# Zenith.net
KiCad netlist of a schematic drawn in EAGLE
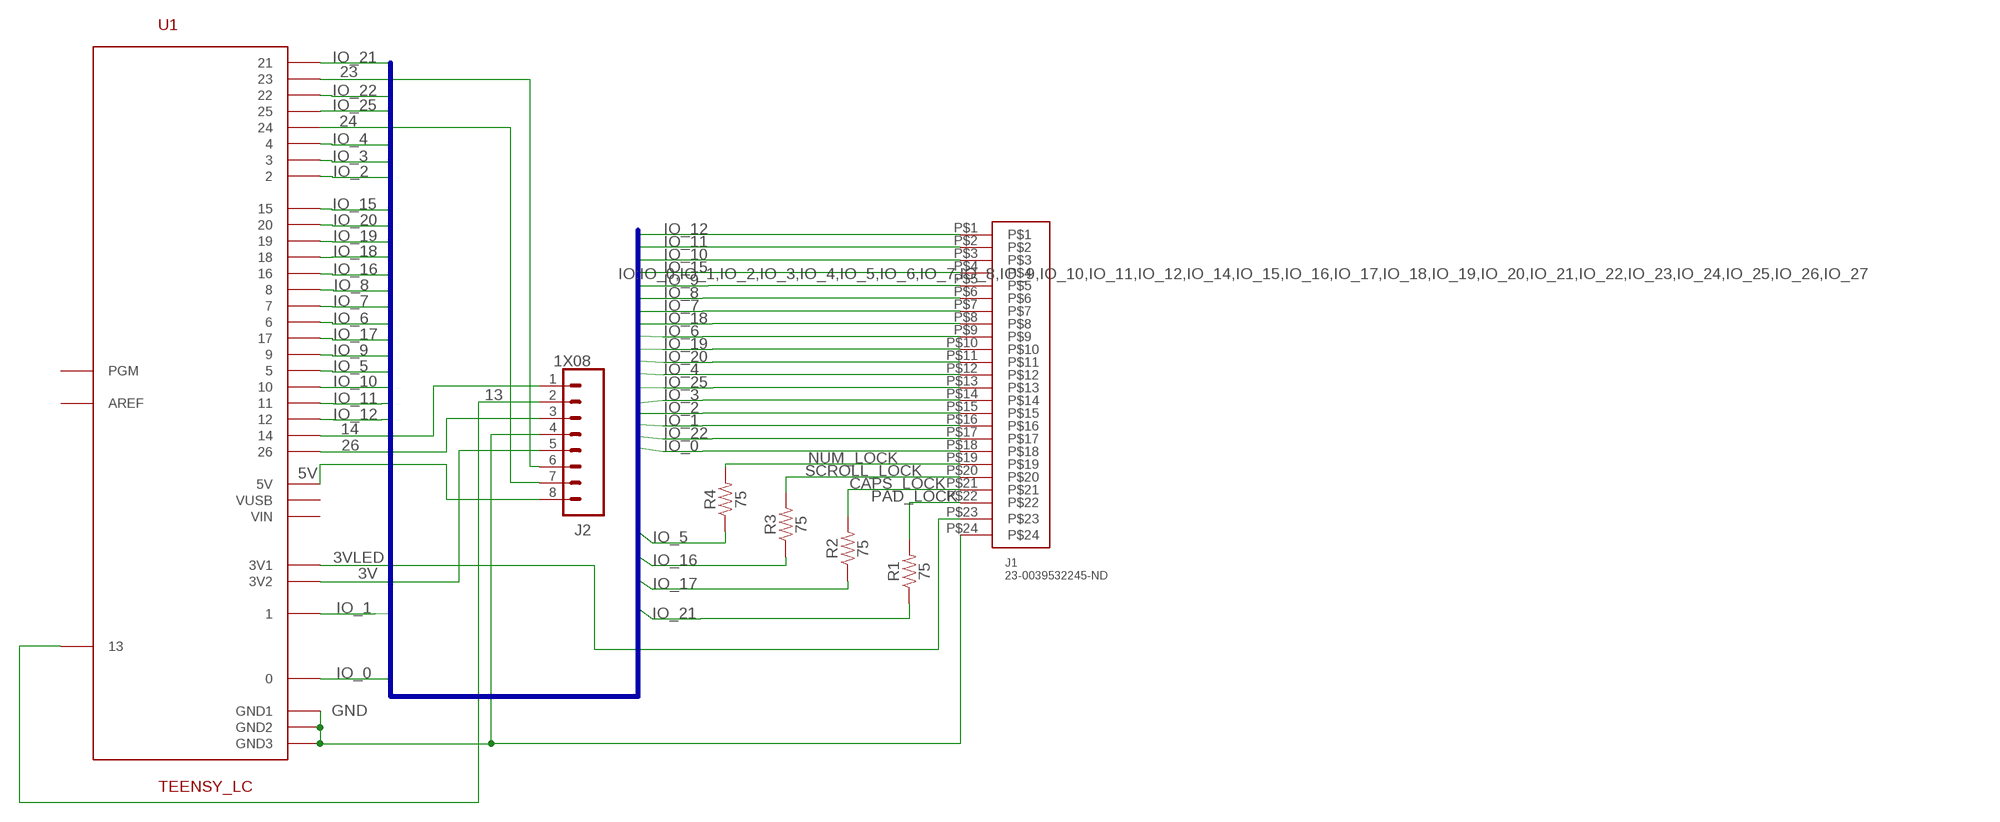
[diagram p0: schematic, sheet 1]

(export (version "E")
  (design (tool "Eeschema 10.0.6"))
  (components
    (comp (ref "J1")
      (value "23-0039532245-ND")
      (footprint "eagle-import:ZENITH_CON")
      (libsource (lib "eagle-import") (part "ZENITH_CON"))
    )
    (comp (ref "J2")
      (value "1X08")
      (footprint "eagle-import:1X08")
      (libsource (lib "eagle-import") (part "CONN_08{dblquote}"))
    )
    (comp (ref "R1")
      (value "75")
      (footprint "eagle-import:AXIAL-0.3")
      (libsource (lib "eagle-import") (part "RESISTOR_AXIAL"))
    )
    (comp (ref "R2")
      (value "75")
      (footprint "eagle-import:AXIAL-0.3")
      (libsource (lib "eagle-import") (part "RESISTOR_AXIAL"))
    )
    (comp (ref "R3")
      (value "75")
      (footprint "eagle-import:AXIAL-0.3")
      (libsource (lib "eagle-import") (part "RESISTOR_AXIAL"))
    )
    (comp (ref "R4")
      (value "75")
      (footprint "eagle-import:AXIAL-0.3")
      (libsource (lib "eagle-import") (part "RESISTOR_AXIAL"))
    )
    (comp (ref "U1")
      (value "TEENSY_LC")
      (footprint "eagle-import:TEENSY_LC")
      (libsource (lib "eagle-import") (part "TEENSY_LC"))
    )
  )
  (nets
    (net (code "7") (name "/3V") (class "Default")
      (node (ref "J2") (pin "5") (pinfunction "5_5") (pintype "passive"))
      (node (ref "U1") (pin "3V2") (pinfunction "3V2_3V2") (pintype "bidirectional"))
    )
    (net (code "8") (name "/3VLED") (class "Default")
      (node (ref "J1") (pin "P$23") (pinfunction "P$23_P$23") (pintype "bidirectional"))
      (node (ref "U1") (pin "3V1") (pinfunction "3V1_3V1") (pintype "bidirectional"))
    )
    (net (code "9") (name "/5V") (class "Default")
      (node (ref "J2") (pin "8") (pinfunction "8_8") (pintype "passive"))
      (node (ref "U1") (pin "5V") (pinfunction "5V_5V") (pintype "bidirectional"))
    )
    (net (code "10") (name "/13") (class "Default")
      (node (ref "J2") (pin "2") (pinfunction "2_2") (pintype "passive"))
      (node (ref "U1") (pin "13") (pinfunction "13_13") (pintype "bidirectional"))
    )
    (net (code "11") (name "/14") (class "Default")
      (node (ref "J2") (pin "1") (pinfunction "1_1") (pintype "passive"))
      (node (ref "U1") (pin "14") (pinfunction "14_14") (pintype "bidirectional"))
    )
    (net (code "12") (name "/23") (class "Default")
      (node (ref "J2") (pin "6") (pinfunction "6_6") (pintype "passive"))
      (node (ref "U1") (pin "23") (pinfunction "23_23") (pintype "bidirectional"))
    )
    (net (code "13") (name "/24") (class "Default")
      (node (ref "J2") (pin "7") (pinfunction "7_7") (pintype "passive"))
      (node (ref "U1") (pin "24") (pinfunction "24_24") (pintype "bidirectional"))
    )
    (net (code "14") (name "/26") (class "Default")
      (node (ref "J2") (pin "3") (pinfunction "3_3") (pintype "passive"))
      (node (ref "U1") (pin "26") (pinfunction "26_26") (pintype "bidirectional"))
    )
    (net (code "15") (name "/CAPS_LOCK") (class "Default")
      (node (ref "J1") (pin "P$21") (pinfunction "P$21_P$21") (pintype "bidirectional"))
      (node (ref "R2") (pin "P$2") (pinfunction "2_P$2") (pintype "passive"))
    )
    (net (code "16") (name "/GND") (class "Default")
      (node (ref "J1") (pin "P$24") (pinfunction "P$24_P$24") (pintype "bidirectional"))
      (node (ref "J2") (pin "4") (pinfunction "4_4") (pintype "passive"))
      (node (ref "U1") (pin "GND1") (pinfunction "GND1_GND1") (pintype "bidirectional"))
      (node (ref "U1") (pin "GND2") (pinfunction "GND2_GND2") (pintype "bidirectional"))
      (node (ref "U1") (pin "GND3") (pinfunction "GND3_GND3") (pintype "bidirectional"))
    )
    (net (code "17") (name "/IO_0") (class "Default")
      (node (ref "J1") (pin "P$18") (pinfunction "P$18_P$18") (pintype "bidirectional"))
      (node (ref "U1") (pin "0") (pinfunction "0_0") (pintype "bidirectional"))
    )
    (net (code "18") (name "/IO_1") (class "Default")
      (node (ref "J1") (pin "P$16") (pinfunction "P$16_P$16") (pintype "bidirectional"))
      (node (ref "U1") (pin "1") (pinfunction "1_1") (pintype "bidirectional"))
    )
    (net (code "19") (name "/IO_2") (class "Default")
      (node (ref "J1") (pin "P$15") (pinfunction "P$15_P$15") (pintype "bidirectional"))
      (node (ref "U1") (pin "2") (pinfunction "2_2") (pintype "bidirectional"))
    )
    (net (code "20") (name "/IO_3") (class "Default")
      (node (ref "J1") (pin "P$14") (pinfunction "P$14_P$14") (pintype "bidirectional"))
      (node (ref "U1") (pin "3") (pinfunction "3_3") (pintype "bidirectional"))
    )
    (net (code "21") (name "/IO_4") (class "Default")
      (node (ref "J1") (pin "P$12") (pinfunction "P$12_P$12") (pintype "bidirectional"))
      (node (ref "U1") (pin "4") (pinfunction "4_4") (pintype "bidirectional"))
    )
    (net (code "22") (name "/IO_5") (class "Default")
      (node (ref "R4") (pin "P$1") (pinfunction "1_P$1") (pintype "passive"))
      (node (ref "U1") (pin "5") (pinfunction "5_5") (pintype "bidirectional"))
    )
    (net (code "23") (name "/IO_6") (class "Default")
      (node (ref "J1") (pin "P$9") (pinfunction "P$9_P$9") (pintype "bidirectional"))
      (node (ref "U1") (pin "6") (pinfunction "6_6") (pintype "bidirectional"))
    )
    (net (code "24") (name "/IO_7") (class "Default")
      (node (ref "J1") (pin "P$7") (pinfunction "P$7_P$7") (pintype "bidirectional"))
      (node (ref "U1") (pin "7") (pinfunction "7_7") (pintype "bidirectional"))
    )
    (net (code "25") (name "/IO_8") (class "Default")
      (node (ref "J1") (pin "P$6") (pinfunction "P$6_P$6") (pintype "bidirectional"))
      (node (ref "U1") (pin "8") (pinfunction "8_8") (pintype "bidirectional"))
    )
    (net (code "26") (name "/IO_9") (class "Default")
      (node (ref "J1") (pin "P$5") (pinfunction "P$5_P$5") (pintype "bidirectional"))
      (node (ref "U1") (pin "9") (pinfunction "9_9") (pintype "bidirectional"))
    )
    (net (code "27") (name "/IO_10") (class "Default")
      (node (ref "J1") (pin "P$3") (pinfunction "P$3_P$3") (pintype "bidirectional"))
      (node (ref "U1") (pin "10") (pinfunction "10_10") (pintype "bidirectional"))
    )
    (net (code "28") (name "/IO_11") (class "Default")
      (node (ref "J1") (pin "P$2") (pinfunction "P$2_P$2") (pintype "bidirectional"))
      (node (ref "U1") (pin "11") (pinfunction "11_11") (pintype "bidirectional"))
    )
    (net (code "29") (name "/IO_12") (class "Default")
      (node (ref "J1") (pin "P$1") (pinfunction "P$1_P$1") (pintype "bidirectional"))
      (node (ref "U1") (pin "12") (pinfunction "12_12") (pintype "bidirectional"))
    )
    (net (code "30") (name "/IO_15") (class "Default")
      (node (ref "J1") (pin "P$4") (pinfunction "P$4_P$4") (pintype "bidirectional"))
      (node (ref "U1") (pin "15") (pinfunction "15_15") (pintype "bidirectional"))
    )
    (net (code "31") (name "/IO_16") (class "Default")
      (node (ref "R3") (pin "P$1") (pinfunction "1_P$1") (pintype "passive"))
      (node (ref "U1") (pin "16") (pinfunction "16_16") (pintype "bidirectional"))
    )
    (net (code "32") (name "/IO_17") (class "Default")
      (node (ref "R2") (pin "P$1") (pinfunction "1_P$1") (pintype "passive"))
      (node (ref "U1") (pin "17") (pinfunction "17_17") (pintype "bidirectional"))
    )
    (net (code "33") (name "/IO_18") (class "Default")
      (node (ref "J1") (pin "P$8") (pinfunction "P$8_P$8") (pintype "bidirectional"))
      (node (ref "U1") (pin "18") (pinfunction "18_18") (pintype "bidirectional"))
    )
    (net (code "34") (name "/IO_19") (class "Default")
      (node (ref "J1") (pin "P$10") (pinfunction "P$10_P$10") (pintype "bidirectional"))
      (node (ref "U1") (pin "19") (pinfunction "19_19") (pintype "bidirectional"))
    )
    (net (code "35") (name "/IO_20") (class "Default")
      (node (ref "J1") (pin "P$11") (pinfunction "P$11_P$11") (pintype "bidirectional"))
      (node (ref "U1") (pin "20") (pinfunction "20_20") (pintype "bidirectional"))
    )
    (net (code "36") (name "/IO_21") (class "Default")
      (node (ref "R1") (pin "P$1") (pinfunction "1_P$1") (pintype "passive"))
      (node (ref "U1") (pin "21") (pinfunction "21_21") (pintype "bidirectional"))
    )
    (net (code "37") (name "/IO_22") (class "Default")
      (node (ref "J1") (pin "P$17") (pinfunction "P$17_P$17") (pintype "bidirectional"))
      (node (ref "U1") (pin "22") (pinfunction "22_22") (pintype "bidirectional"))
    )
    (net (code "38") (name "/IO_25") (class "Default")
      (node (ref "J1") (pin "P$13") (pinfunction "P$13_P$13") (pintype "bidirectional"))
      (node (ref "U1") (pin "25") (pinfunction "25_25") (pintype "bidirectional"))
    )
    (net (code "39") (name "/NUM_LOCK") (class "Default")
      (node (ref "J1") (pin "P$19") (pinfunction "P$19_P$19") (pintype "bidirectional"))
      (node (ref "R4") (pin "P$2") (pinfunction "2_P$2") (pintype "passive"))
    )
    (net (code "40") (name "/PAD_LOCK") (class "Default")
      (node (ref "J1") (pin "P$22") (pinfunction "P$22_P$22") (pintype "bidirectional"))
      (node (ref "R1") (pin "P$2") (pinfunction "2_P$2") (pintype "passive"))
    )
    (net (code "41") (name "/SCROLL_LOCK") (class "Default")
      (node (ref "J1") (pin "P$20") (pinfunction "P$20_P$20") (pintype "bidirectional"))
      (node (ref "R3") (pin "P$2") (pinfunction "2_P$2") (pintype "passive"))
    )
    (net (code "43") (name "unconnected-(U1-PadAREF)") (class "Default")
      (node (ref "U1") (pin "AREF") (pinfunction "AREF_AREF") (pintype "bidirectional"))
    )
    (net (code "44") (name "unconnected-(U1-PadPGM)") (class "Default")
      (node (ref "U1") (pin "PGM") (pinfunction "PGM_PGM") (pintype "bidirectional"))
    )
    (net (code "45") (name "unconnected-(U1-PadVIN)") (class "Default")
      (node (ref "U1") (pin "VIN") (pinfunction "VIN_VIN") (pintype "bidirectional"))
    )
    (net (code "46") (name "unconnected-(U1-PadVUSB)") (class "Default")
      (node (ref "U1") (pin "VUSB") (pinfunction "VUSB_VUSB") (pintype "bidirectional"))
    )
  )
)
